# tx_mini_buck.net
KiCad netlist of a schematic drawn in Altium Designer
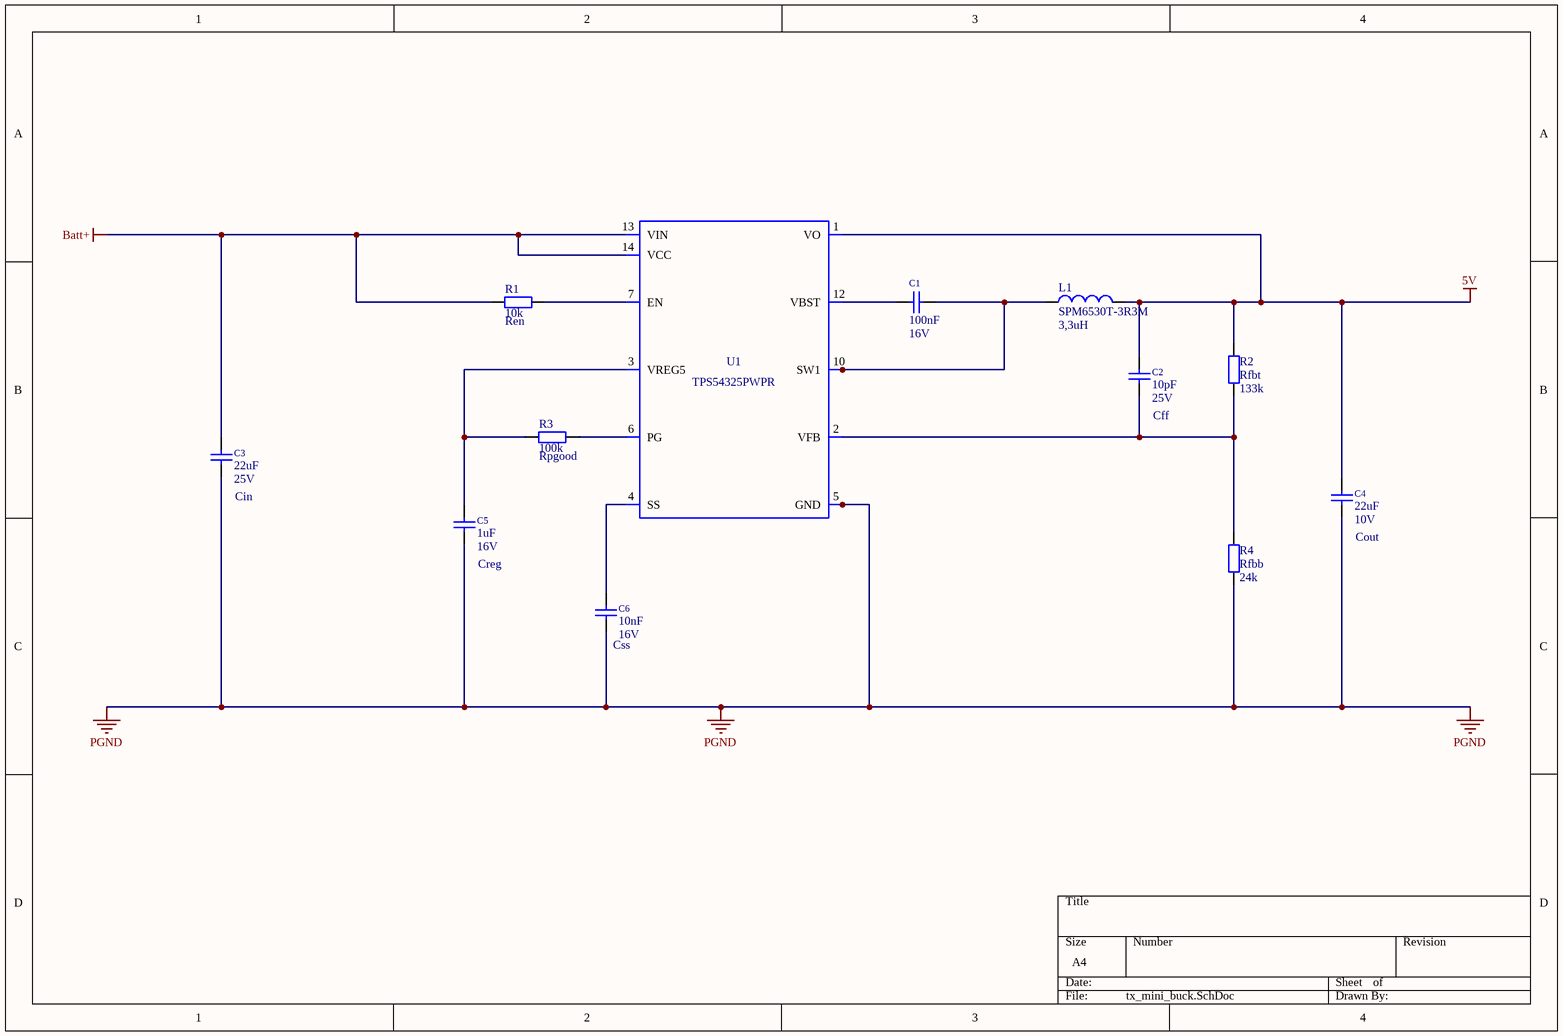
[diagram p0: tx_mini_buck.SchDoc]

(export (version "E")
  (design (tool "Eeschema 10.0.6"))
  (components
    (comp (ref "C1")
      (value "100nF")
      (footprint "C0402")
      (description "Capacitor")
      (fields (field (name "VOLTAGE") "16V"))
      (libsource (lib "Toni") (part "C 100nF 0402"))
    )
    (comp (ref "C2")
      (value "10pF")
      (footprint "C0402")
      (description "Capacitor")
      (fields (field (name "VOLTAGE") "25V") (field (name "BEZEICHNUNG") "Cff"))
      (libsource (lib "Toni") (part "C"))
    )
    (comp (ref "C3")
      (value "22uF")
      (footprint "C1210")
      (description "Capacitor")
      (fields (field (name "VOLTAGE") "25V") (field (name "BEZEICHNUNG") "Cin"))
      (libsource (lib "Toni") (part "C"))
    )
    (comp (ref "C4")
      (value "22uF")
      (footprint "C1206")
      (description "Capacitor")
      (fields (field (name "VOLTAGE") "10V") (field (name "BEZEICHNUNG") "Cout"))
      (libsource (lib "Toni") (part "C"))
    )
    (comp (ref "C5")
      (value "1uF")
      (footprint "C0603")
      (description "Capacitor")
      (fields (field (name "VOLTAGE") "16V") (field (name "BEZEICHNUNG") "Creg"))
      (libsource (lib "Toni") (part "C"))
    )
    (comp (ref "C6")
      (value "10nF")
      (footprint "C0402")
      (description "Capacitor")
      (fields (field (name "VOLTAGE") "16V") (field (name "BEZEICHNUNG") "Css"))
      (libsource (lib "Toni") (part "C"))
    )
    (comp (ref "L1")
      (value "Inductance")
      (footprint "SPM6530")
      (description "Power Inductance")
      (fields (field (name "HERST.BEZ.:") "SPM6530T-3R3M") (field (name "INDUCTANCE") "3,3uH"))
      (libsource (lib "Toni") (part "L power"))
    )
    (comp (ref "R1")
      (value "10k")
      (footprint "RES0402")
      (description "Resistor")
      (fields (field (name "BEZEICHNUNG") "Ren") (field (name "Comment") "R"))
      (libsource (lib "") (part "R_1"))
    )
    (comp (ref "R2")
      (value "133k")
      (footprint "RES0402")
      (description "Resistor")
      (fields (field (name "BEZEICHNUNG") "Rfbt") (field (name "Comment") "R"))
      (libsource (lib "Toni") (part "R"))
    )
    (comp (ref "R3")
      (value "100k")
      (footprint "RES0402")
      (description "Resistor")
      (fields (field (name "BEZEICHNUNG") "Rpgood") (field (name "Comment") "R"))
      (libsource (lib "") (part "R_1"))
    )
    (comp (ref "R4")
      (value "24k")
      (footprint "RES0603")
      (description "Resistor")
      (fields (field (name "BEZEICHNUNG") "Rfbb") (field (name "Comment") "R"))
      (libsource (lib "Toni") (part "R"))
    )
    (comp (ref "U1")
      (value "TPS54225PWP")
      (footprint "R-PDSO-G14")
      (description "TPS54325PWPR")
      (fields (field (name "PACKAGEREFERENCE") "TPS54325PWPR"))
      (libsource (lib "TI WEBENCH") (part "U1"))
    )
  )
  (nets
    (net (code "1") (name "5V") (class "Default")
      (node (ref "C2") (pin "1") (pinfunction "1_1") (pintype "passive"))
      (node (ref "C4") (pin "1") (pinfunction "1_1") (pintype "passive"))
      (node (ref "L1") (pin "2") (pinfunction "2_2") (pintype "passive"))
      (node (ref "R2") (pin "2") (pinfunction "2_2") (pintype "passive"))
      (node (ref "U1") (pin "1") (pinfunction "VO_1") (pintype "passive"))
    )
    (net (code "2") (name "Batt+") (class "Default")
      (node (ref "C3") (pin "1") (pinfunction "1_1") (pintype "passive"))
      (node (ref "R1") (pin "1") (pinfunction "1_1") (pintype "passive"))
      (node (ref "U1") (pin "13") (pinfunction "VIN_13") (pintype "passive"))
      (node (ref "U1") (pin "14") (pinfunction "VCC_14") (pintype "passive"))
    )
    (net (code "3") (name "Net-(U1-EN)") (class "Default")
      (node (ref "R1") (pin "2") (pinfunction "2_2") (pintype "passive"))
      (node (ref "U1") (pin "7") (pinfunction "EN_7") (pintype "passive"))
    )
    (net (code "4") (name "Net-(U1-PG)") (class "Default")
      (node (ref "R3") (pin "2") (pinfunction "2_2") (pintype "passive"))
      (node (ref "U1") (pin "6") (pinfunction "PG_6") (pintype "passive"))
    )
    (net (code "5") (name "Net-(U1-SS)") (class "Default")
      (node (ref "C6") (pin "1") (pinfunction "1_1") (pintype "passive"))
      (node (ref "U1") (pin "4") (pinfunction "SS_4") (pintype "passive"))
    )
    (net (code "6") (name "Net-(U1-SW1)") (class "Default")
      (node (ref "C1") (pin "2") (pinfunction "2_2") (pintype "passive"))
      (node (ref "L1") (pin "1") (pinfunction "1_1") (pintype "passive"))
      (node (ref "U1") (pin "10") (pinfunction "SW1_10") (pintype "passive"))
      (node (ref "U1") (pin "11") (pinfunction "SW2_11") (pintype "passive"))
    )
    (net (code "7") (name "Net-(U1-VBST)") (class "Default")
      (node (ref "C1") (pin "1") (pinfunction "1_1") (pintype "passive"))
      (node (ref "U1") (pin "12") (pinfunction "VBST_12") (pintype "passive"))
    )
    (net (code "8") (name "Net-(U1-VFB)") (class "Default")
      (node (ref "C2") (pin "2") (pinfunction "2_2") (pintype "passive"))
      (node (ref "R2") (pin "1") (pinfunction "1_1") (pintype "passive"))
      (node (ref "R4") (pin "2") (pinfunction "2_2") (pintype "passive"))
      (node (ref "U1") (pin "2") (pinfunction "VFB_2") (pintype "passive"))
    )
    (net (code "9") (name "Net-(U1-VREG5)") (class "Default")
      (node (ref "C5") (pin "1") (pinfunction "1_1") (pintype "passive"))
      (node (ref "R3") (pin "1") (pinfunction "1_1") (pintype "passive"))
      (node (ref "U1") (pin "3") (pinfunction "VREG5_3") (pintype "passive"))
    )
    (net (code "10") (name "PGND") (class "Default")
      (node (ref "C3") (pin "2") (pinfunction "2_2") (pintype "passive"))
      (node (ref "C4") (pin "2") (pinfunction "2_2") (pintype "passive"))
      (node (ref "C5") (pin "2") (pinfunction "2_2") (pintype "passive"))
      (node (ref "C6") (pin "2") (pinfunction "2_2") (pintype "passive"))
      (node (ref "R4") (pin "1") (pinfunction "1_1") (pintype "passive"))
      (node (ref "U1") (pin "15") (pinfunction "ETPAD_15") (pintype "passive"))
      (node (ref "U1") (pin "5") (pinfunction "GND_5") (pintype "passive"))
      (node (ref "U1") (pin "8") (pinfunction "PGND1_8") (pintype "passive"))
      (node (ref "U1") (pin "9") (pinfunction "PGND2_9") (pintype "passive"))
    )
  )
)
